# Length_Tune.net
KiCad netlist of a schematic drawn in Altium Designer
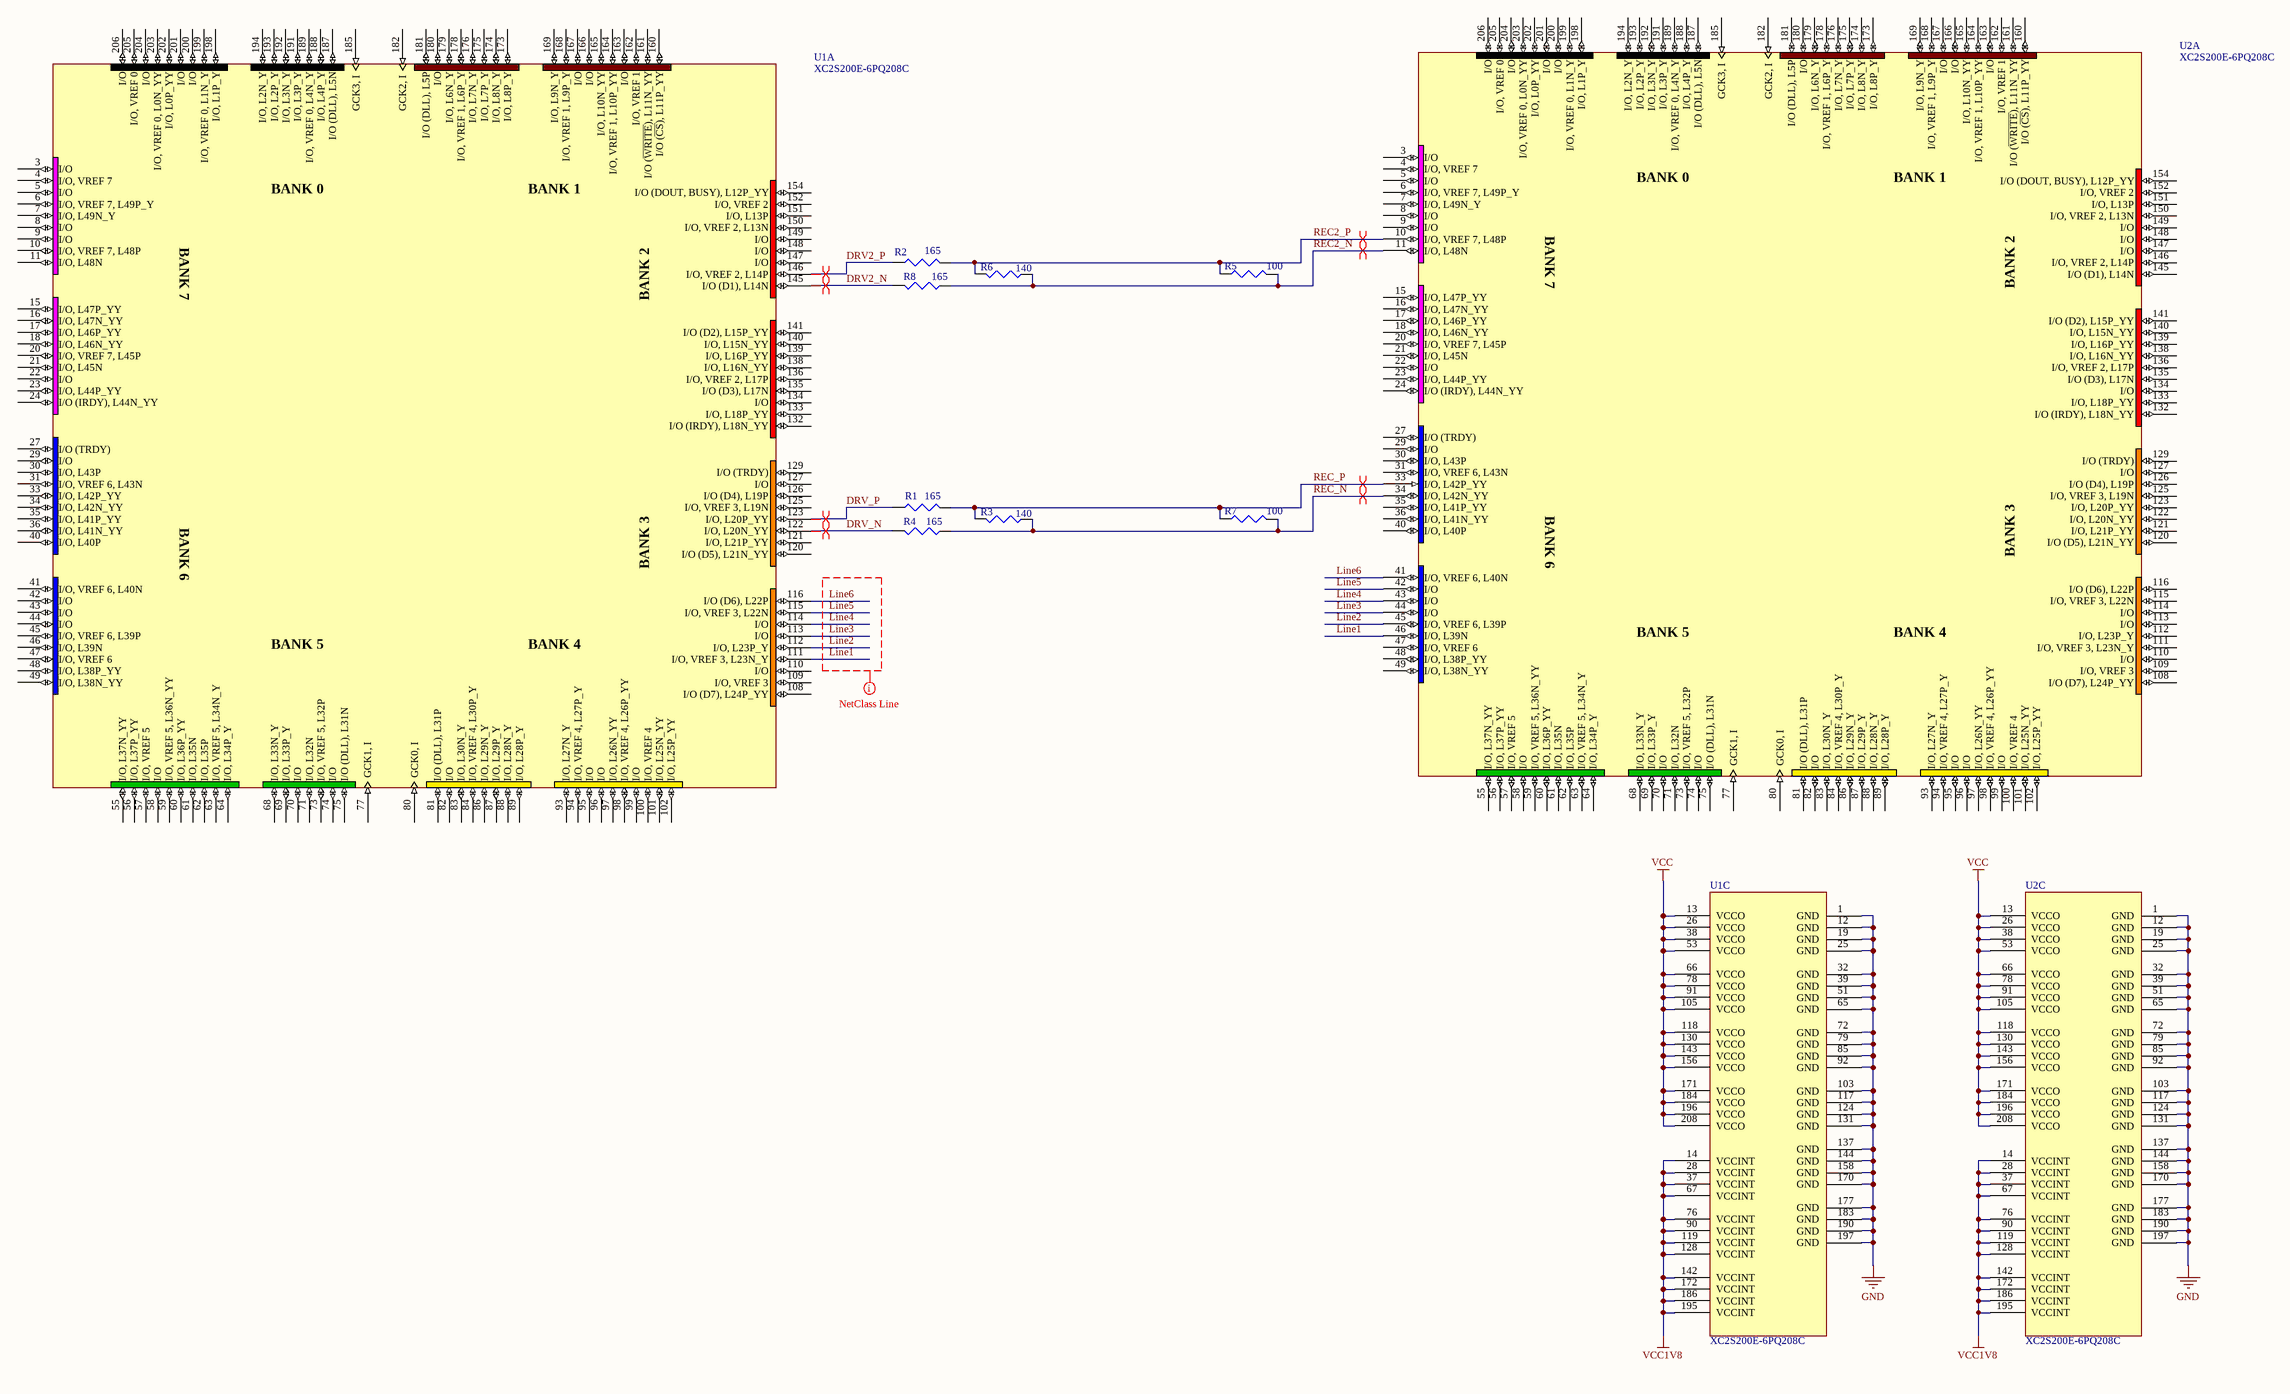
[diagram p0: Length_Tune.SchDoc]

(export (version "E")
  (design (tool "Eeschema 10.0.6"))
  (components
    (comp (ref "R1")
      (value "165")
      (footprint "J1-0603")
      (description "Resistor")
      (fields (field (name "Comment") "Res3") (field (name "PUBLISHER") "Altium Limited"))
      (libsource (lib "Miscellaneous Devices") (part "Res3"))
    )
    (comp (ref "R2")
      (value "165")
      (footprint "J1-0603")
      (description "Resistor")
      (fields (field (name "Comment") "Res3") (field (name "PUBLISHER") "Altium Limited"))
      (libsource (lib "Miscellaneous Devices") (part "Res3"))
    )
    (comp (ref "R3")
      (value "140")
      (footprint "J1-0603")
      (description "Resistor")
      (fields (field (name "Comment") "Res3") (field (name "PUBLISHER") "Altium Limited"))
      (libsource (lib "Miscellaneous Devices") (part "Res3"))
    )
    (comp (ref "R4")
      (value "165")
      (footprint "J1-0603")
      (description "Resistor")
      (fields (field (name "Comment") "Res3") (field (name "PUBLISHER") "Altium Limited"))
      (libsource (lib "Miscellaneous Devices") (part "Res3"))
    )
    (comp (ref "R5")
      (value "100")
      (footprint "J1-0603")
      (description "Resistor")
      (fields (field (name "Comment") "Res3") (field (name "PUBLISHER") "Altium Limited"))
      (libsource (lib "Miscellaneous Devices") (part "Res3"))
    )
    (comp (ref "R6")
      (value "140")
      (footprint "J1-0603")
      (description "Resistor")
      (fields (field (name "Comment") "Res3") (field (name "PUBLISHER") "Altium Limited"))
      (libsource (lib "Miscellaneous Devices") (part "Res3"))
    )
    (comp (ref "R7")
      (value "100")
      (footprint "J1-0603")
      (description "Resistor")
      (fields (field (name "Comment") "Res3") (field (name "PUBLISHER") "Altium Limited"))
      (libsource (lib "Miscellaneous Devices") (part "Res3"))
    )
    (comp (ref "R8")
      (value "165")
      (footprint "J1-0603")
      (description "Resistor")
      (fields (field (name "Comment") "Res3") (field (name "PUBLISHER") "Altium Limited"))
      (libsource (lib "Miscellaneous Devices") (part "Res3"))
    )
    (comp (ref "U1")
      (value "XC2S200E-6PQ208C")
      (footprint "PQ208")
      (description "Spartan-IIE 1.8V FPGA, 208-Pin PQFP, Standard Performance, Commercial Grade")
      (fields (field (name "PUBLISHER") "Altium Limited"))
      (libsource (lib "Xilinx Spartan-IIE") (part "XC2S200E-6PQ208C"))
    )
    (comp (ref "U2")
      (value "XC2S200E-6PQ208C")
      (footprint "PQ208")
      (description "Spartan-IIE 1.8V FPGA, 208-Pin PQFP, Standard Performance, Commercial Grade")
      (fields (field (name "PUBLISHER") "Altium Limited"))
      (libsource (lib "Xilinx Spartan-IIE") (part "XC2S200E-6PQ208C"))
    )
  )
  (nets
    (net (code "1") (name "/DRV2_N") (class "Default")
      (node (ref "R8") (pin "2") (pinfunction "2_2") (pintype "passive"))
      (node (ref "U1") (pin "145") (pinfunction "I/O_(D1),_L14N_145") (pintype "bidirectional"))
    )
    (net (code "2") (name "/DRV2_P") (class "Default")
      (node (ref "R2") (pin "1") (pinfunction "1_1") (pintype "passive"))
      (node (ref "U1") (pin "146") (pinfunction "I/O,_VREF_2,_L14P_146") (pintype "bidirectional"))
    )
    (net (code "3") (name "/DRV_N") (class "Default")
      (node (ref "R4") (pin "2") (pinfunction "2_2") (pintype "passive"))
      (node (ref "U1") (pin "122") (pinfunction "I/O,_L20N_YY_122") (pintype "bidirectional"))
    )
    (net (code "4") (name "/DRV_P") (class "Default")
      (node (ref "R1") (pin "1") (pinfunction "1_1") (pintype "passive"))
      (node (ref "U1") (pin "123") (pinfunction "I/O,_L20P_YY_123") (pintype "bidirectional"))
    )
    (net (code "5") (name "/Line1") (class "Default")
      (node (ref "U1") (pin "111") (pinfunction "I/O,_VREF_3,_L23N_Y_111") (pintype "bidirectional"))
      (node (ref "U2") (pin "46") (pinfunction "I/O,_L39N_46") (pintype "bidirectional"))
    )
    (net (code "6") (name "/Line2") (class "Default")
      (node (ref "U1") (pin "112") (pinfunction "I/O,_L23P_Y_112") (pintype "bidirectional"))
      (node (ref "U2") (pin "45") (pinfunction "I/O,_VREF_6,_L39P_45") (pintype "bidirectional"))
    )
    (net (code "7") (name "/Line3") (class "Default")
      (node (ref "U1") (pin "113") (pinfunction "I/O_113") (pintype "bidirectional"))
      (node (ref "U2") (pin "44") (pinfunction "I/O_44") (pintype "bidirectional"))
    )
    (net (code "8") (name "/Line4") (class "Default")
      (node (ref "U1") (pin "114") (pinfunction "I/O_114") (pintype "bidirectional"))
      (node (ref "U2") (pin "43") (pinfunction "I/O_43") (pintype "bidirectional"))
    )
    (net (code "9") (name "/Line5") (class "Default")
      (node (ref "U1") (pin "115") (pinfunction "I/O,_VREF_3,_L22N_115") (pintype "bidirectional"))
      (node (ref "U2") (pin "42") (pinfunction "I/O_42") (pintype "bidirectional"))
    )
    (net (code "10") (name "/Line6") (class "Default")
      (node (ref "U1") (pin "116") (pinfunction "I/O_(D6),_L22P_116") (pintype "bidirectional"))
      (node (ref "U2") (pin "41") (pinfunction "I/O,_VREF_6,_L40N_41") (pintype "bidirectional"))
    )
    (net (code "11") (name "/REC2_N") (class "Default")
      (node (ref "R5") (pin "2") (pinfunction "2_2") (pintype "passive"))
      (node (ref "R6") (pin "1") (pinfunction "1_1") (pintype "passive"))
      (node (ref "R8") (pin "1") (pinfunction "1_1") (pintype "passive"))
      (node (ref "U2") (pin "11") (pinfunction "I/O,_L48N_11") (pintype "bidirectional"))
    )
    (net (code "12") (name "/REC2_P") (class "Default")
      (node (ref "R2") (pin "2") (pinfunction "2_2") (pintype "passive"))
      (node (ref "R5") (pin "1") (pinfunction "1_1") (pintype "passive"))
      (node (ref "R6") (pin "2") (pinfunction "2_2") (pintype "passive"))
      (node (ref "U2") (pin "10") (pinfunction "I/O,_VREF_7,_L48P_10") (pintype "bidirectional"))
    )
    (net (code "13") (name "/REC_N") (class "Default")
      (node (ref "R3") (pin "1") (pinfunction "1_1") (pintype "passive"))
      (node (ref "R4") (pin "1") (pinfunction "1_1") (pintype "passive"))
      (node (ref "R7") (pin "2") (pinfunction "2_2") (pintype "passive"))
      (node (ref "U2") (pin "34") (pinfunction "I/O,_L42N_YY_34") (pintype "bidirectional"))
    )
    (net (code "14") (name "/REC_P") (class "Default")
      (node (ref "R1") (pin "2") (pinfunction "2_2") (pintype "passive"))
      (node (ref "R3") (pin "2") (pinfunction "2_2") (pintype "passive"))
      (node (ref "R7") (pin "1") (pinfunction "1_1") (pintype "passive"))
      (node (ref "U2") (pin "33") (pinfunction "I/O,_L42P_YY_33") (pintype "bidirectional"))
    )
    (net (code "15") (name "GND") (class "Default")
      (node (ref "U1") (pin "1") (pinfunction "GND_1") (pintype "power_in"))
      (node (ref "U1") (pin "103") (pinfunction "GND_103") (pintype "power_in"))
      (node (ref "U1") (pin "117") (pinfunction "GND_117") (pintype "power_in"))
      (node (ref "U1") (pin "12") (pinfunction "GND_12") (pintype "power_in"))
      (node (ref "U1") (pin "124") (pinfunction "GND_124") (pintype "power_in"))
      (node (ref "U1") (pin "131") (pinfunction "GND_131") (pintype "power_in"))
      (node (ref "U1") (pin "137") (pinfunction "GND_137") (pintype "power_in"))
      (node (ref "U1") (pin "144") (pinfunction "GND_144") (pintype "power_in"))
      (node (ref "U1") (pin "158") (pinfunction "GND_158") (pintype "power_in"))
      (node (ref "U1") (pin "170") (pinfunction "GND_170") (pintype "power_in"))
      (node (ref "U1") (pin "177") (pinfunction "GND_177") (pintype "power_in"))
      (node (ref "U1") (pin "183") (pinfunction "GND_183") (pintype "power_in"))
      (node (ref "U1") (pin "19") (pinfunction "GND_19") (pintype "power_in"))
      (node (ref "U1") (pin "190") (pinfunction "GND_190") (pintype "power_in"))
      (node (ref "U1") (pin "197") (pinfunction "GND_197") (pintype "power_in"))
      (node (ref "U1") (pin "25") (pinfunction "GND_25") (pintype "power_in"))
      (node (ref "U1") (pin "32") (pinfunction "GND_32") (pintype "power_in"))
      (node (ref "U1") (pin "39") (pinfunction "GND_39") (pintype "power_in"))
      (node (ref "U1") (pin "51") (pinfunction "GND_51") (pintype "power_in"))
      (node (ref "U1") (pin "65") (pinfunction "GND_65") (pintype "power_in"))
      (node (ref "U1") (pin "72") (pinfunction "GND_72") (pintype "power_in"))
      (node (ref "U1") (pin "79") (pinfunction "GND_79") (pintype "power_in"))
      (node (ref "U1") (pin "85") (pinfunction "GND_85") (pintype "power_in"))
      (node (ref "U1") (pin "92") (pinfunction "GND_92") (pintype "power_in"))
      (node (ref "U2") (pin "1") (pinfunction "GND_1") (pintype "power_in"))
      (node (ref "U2") (pin "103") (pinfunction "GND_103") (pintype "power_in"))
      (node (ref "U2") (pin "117") (pinfunction "GND_117") (pintype "power_in"))
      (node (ref "U2") (pin "12") (pinfunction "GND_12") (pintype "power_in"))
      (node (ref "U2") (pin "124") (pinfunction "GND_124") (pintype "power_in"))
      (node (ref "U2") (pin "131") (pinfunction "GND_131") (pintype "power_in"))
      (node (ref "U2") (pin "137") (pinfunction "GND_137") (pintype "power_in"))
      (node (ref "U2") (pin "144") (pinfunction "GND_144") (pintype "power_in"))
      (node (ref "U2") (pin "158") (pinfunction "GND_158") (pintype "power_in"))
      (node (ref "U2") (pin "170") (pinfunction "GND_170") (pintype "power_in"))
      (node (ref "U2") (pin "177") (pinfunction "GND_177") (pintype "power_in"))
      (node (ref "U2") (pin "183") (pinfunction "GND_183") (pintype "power_in"))
      (node (ref "U2") (pin "19") (pinfunction "GND_19") (pintype "power_in"))
      (node (ref "U2") (pin "190") (pinfunction "GND_190") (pintype "power_in"))
      (node (ref "U2") (pin "197") (pinfunction "GND_197") (pintype "power_in"))
      (node (ref "U2") (pin "25") (pinfunction "GND_25") (pintype "power_in"))
      (node (ref "U2") (pin "32") (pinfunction "GND_32") (pintype "power_in"))
      (node (ref "U2") (pin "39") (pinfunction "GND_39") (pintype "power_in"))
      (node (ref "U2") (pin "51") (pinfunction "GND_51") (pintype "power_in"))
      (node (ref "U2") (pin "65") (pinfunction "GND_65") (pintype "power_in"))
      (node (ref "U2") (pin "72") (pinfunction "GND_72") (pintype "power_in"))
      (node (ref "U2") (pin "79") (pinfunction "GND_79") (pintype "power_in"))
      (node (ref "U2") (pin "85") (pinfunction "GND_85") (pintype "power_in"))
      (node (ref "U2") (pin "92") (pinfunction "GND_92") (pintype "power_in"))
    )
    (net (code "16") (name "VCC") (class "Default")
      (node (ref "U1") (pin "105") (pinfunction "VCCO_105") (pintype "power_in"))
      (node (ref "U1") (pin "118") (pinfunction "VCCO_118") (pintype "power_in"))
      (node (ref "U1") (pin "13") (pinfunction "VCCO_13") (pintype "power_in"))
      (node (ref "U1") (pin "130") (pinfunction "VCCO_130") (pintype "power_in"))
      (node (ref "U1") (pin "143") (pinfunction "VCCO_143") (pintype "power_in"))
      (node (ref "U1") (pin "156") (pinfunction "VCCO_156") (pintype "power_in"))
      (node (ref "U1") (pin "171") (pinfunction "VCCO_171") (pintype "power_in"))
      (node (ref "U1") (pin "184") (pinfunction "VCCO_184") (pintype "power_in"))
      (node (ref "U1") (pin "196") (pinfunction "VCCO_196") (pintype "power_in"))
      (node (ref "U1") (pin "208") (pinfunction "VCCO_208") (pintype "power_in"))
      (node (ref "U1") (pin "26") (pinfunction "VCCO_26") (pintype "power_in"))
      (node (ref "U1") (pin "38") (pinfunction "VCCO_38") (pintype "power_in"))
      (node (ref "U1") (pin "53") (pinfunction "VCCO_53") (pintype "power_in"))
      (node (ref "U1") (pin "66") (pinfunction "VCCO_66") (pintype "power_in"))
      (node (ref "U1") (pin "78") (pinfunction "VCCO_78") (pintype "power_in"))
      (node (ref "U1") (pin "91") (pinfunction "VCCO_91") (pintype "power_in"))
      (node (ref "U2") (pin "105") (pinfunction "VCCO_105") (pintype "power_in"))
      (node (ref "U2") (pin "118") (pinfunction "VCCO_118") (pintype "power_in"))
      (node (ref "U2") (pin "13") (pinfunction "VCCO_13") (pintype "power_in"))
      (node (ref "U2") (pin "130") (pinfunction "VCCO_130") (pintype "power_in"))
      (node (ref "U2") (pin "143") (pinfunction "VCCO_143") (pintype "power_in"))
      (node (ref "U2") (pin "156") (pinfunction "VCCO_156") (pintype "power_in"))
      (node (ref "U2") (pin "171") (pinfunction "VCCO_171") (pintype "power_in"))
      (node (ref "U2") (pin "184") (pinfunction "VCCO_184") (pintype "power_in"))
      (node (ref "U2") (pin "196") (pinfunction "VCCO_196") (pintype "power_in"))
      (node (ref "U2") (pin "208") (pinfunction "VCCO_208") (pintype "power_in"))
      (node (ref "U2") (pin "26") (pinfunction "VCCO_26") (pintype "power_in"))
      (node (ref "U2") (pin "38") (pinfunction "VCCO_38") (pintype "power_in"))
      (node (ref "U2") (pin "53") (pinfunction "VCCO_53") (pintype "power_in"))
      (node (ref "U2") (pin "66") (pinfunction "VCCO_66") (pintype "power_in"))
      (node (ref "U2") (pin "78") (pinfunction "VCCO_78") (pintype "power_in"))
      (node (ref "U2") (pin "91") (pinfunction "VCCO_91") (pintype "power_in"))
    )
    (net (code "17") (name "VCC1V8") (class "Default")
      (node (ref "U1") (pin "119") (pinfunction "VCCINT_119") (pintype "power_in"))
      (node (ref "U1") (pin "128") (pinfunction "VCCINT_128") (pintype "power_in"))
      (node (ref "U1") (pin "14") (pinfunction "VCCINT_14") (pintype "power_in"))
      (node (ref "U1") (pin "142") (pinfunction "VCCINT_142") (pintype "power_in"))
      (node (ref "U1") (pin "172") (pinfunction "VCCINT_172") (pintype "power_in"))
      (node (ref "U1") (pin "186") (pinfunction "VCCINT_186") (pintype "power_in"))
      (node (ref "U1") (pin "195") (pinfunction "VCCINT_195") (pintype "power_in"))
      (node (ref "U1") (pin "28") (pinfunction "VCCINT_28") (pintype "power_in"))
      (node (ref "U1") (pin "37") (pinfunction "VCCINT_37") (pintype "power_in"))
      (node (ref "U1") (pin "67") (pinfunction "VCCINT_67") (pintype "power_in"))
      (node (ref "U1") (pin "76") (pinfunction "VCCINT_76") (pintype "power_in"))
      (node (ref "U1") (pin "90") (pinfunction "VCCINT_90") (pintype "power_in"))
      (node (ref "U2") (pin "119") (pinfunction "VCCINT_119") (pintype "power_in"))
      (node (ref "U2") (pin "128") (pinfunction "VCCINT_128") (pintype "power_in"))
      (node (ref "U2") (pin "14") (pinfunction "VCCINT_14") (pintype "power_in"))
      (node (ref "U2") (pin "142") (pinfunction "VCCINT_142") (pintype "power_in"))
      (node (ref "U2") (pin "172") (pinfunction "VCCINT_172") (pintype "power_in"))
      (node (ref "U2") (pin "186") (pinfunction "VCCINT_186") (pintype "power_in"))
      (node (ref "U2") (pin "195") (pinfunction "VCCINT_195") (pintype "power_in"))
      (node (ref "U2") (pin "28") (pinfunction "VCCINT_28") (pintype "power_in"))
      (node (ref "U2") (pin "37") (pinfunction "VCCINT_37") (pintype "power_in"))
      (node (ref "U2") (pin "67") (pinfunction "VCCINT_67") (pintype "power_in"))
      (node (ref "U2") (pin "76") (pinfunction "VCCINT_76") (pintype "power_in"))
      (node (ref "U2") (pin "90") (pinfunction "VCCINT_90") (pintype "power_in"))
    )
    (net (code "18") (name "unconnected-(U1A-GCK0,_I-Pad80)") (class "Default")
      (node (ref "U1") (pin "80") (pinfunction "GCK0,_I_80") (pintype "input"))
    )
    (net (code "19") (name "unconnected-(U1A-GCK1,_I-Pad77)") (class "Default")
      (node (ref "U1") (pin "77") (pinfunction "GCK1,_I_77") (pintype "input"))
    )
    (net (code "20") (name "unconnected-(U1A-GCK2,_I-Pad182)") (class "Default")
      (node (ref "U1") (pin "182") (pinfunction "GCK2,_I_182") (pintype "input"))
    )
    (net (code "21") (name "unconnected-(U1A-GCK3,_I-Pad185)") (class "Default")
      (node (ref "U1") (pin "185") (pinfunction "GCK3,_I_185") (pintype "input"))
    )
    (net (code "22") (name "unconnected-(U1A-I{slash}O,_L0P_YY-Pad202)") (class "Default")
      (node (ref "U1") (pin "202") (pinfunction "I/O,_L0P_YY_202") (pintype "bidirectional"))
    )
    (net (code "23") (name "unconnected-(U1A-I{slash}O,_L1P_Y-Pad198)") (class "Default")
      (node (ref "U1") (pin "198") (pinfunction "I/O,_L1P_Y_198") (pintype "bidirectional"))
    )
    (net (code "24") (name "unconnected-(U1A-I{slash}O,_L2N_Y-Pad194)") (class "Default")
      (node (ref "U1") (pin "194") (pinfunction "I/O,_L2N_Y_194") (pintype "bidirectional"))
    )
    (net (code "25") (name "unconnected-(U1A-I{slash}O,_L2P_Y-Pad193)") (class "Default")
      (node (ref "U1") (pin "193") (pinfunction "I/O,_L2P_Y_193") (pintype "bidirectional"))
    )
    (net (code "26") (name "unconnected-(U1A-I{slash}O,_L3N_Y-Pad192)") (class "Default")
      (node (ref "U1") (pin "192") (pinfunction "I/O,_L3N_Y_192") (pintype "bidirectional"))
    )
    (net (code "27") (name "unconnected-(U1A-I{slash}O,_L3P_Y-Pad191)") (class "Default")
      (node (ref "U1") (pin "191") (pinfunction "I/O,_L3P_Y_191") (pintype "bidirectional"))
    )
    (net (code "28") (name "unconnected-(U1A-I{slash}O,_L4P_Y-Pad188)") (class "Default")
      (node (ref "U1") (pin "188") (pinfunction "I/O,_L4P_Y_188") (pintype "bidirectional"))
    )
    (net (code "29") (name "unconnected-(U1A-I{slash}O,_L6N_Y-Pad179)") (class "Default")
      (node (ref "U1") (pin "179") (pinfunction "I/O,_L6N_Y_179") (pintype "bidirectional"))
    )
    (net (code "30") (name "unconnected-(U1A-I{slash}O,_L7N_Y-Pad176)") (class "Default")
      (node (ref "U1") (pin "176") (pinfunction "I/O,_L7N_Y_176") (pintype "bidirectional"))
    )
    (net (code "31") (name "unconnected-(U1A-I{slash}O,_L7P_Y-Pad175)") (class "Default")
      (node (ref "U1") (pin "175") (pinfunction "I/O,_L7P_Y_175") (pintype "bidirectional"))
    )
    (net (code "32") (name "unconnected-(U1A-I{slash}O,_L8N_Y-Pad174)") (class "Default")
      (node (ref "U1") (pin "174") (pinfunction "I/O,_L8N_Y_174") (pintype "bidirectional"))
    )
    (net (code "33") (name "unconnected-(U1A-I{slash}O,_L8P_Y-Pad173)") (class "Default")
      (node (ref "U1") (pin "173") (pinfunction "I/O,_L8P_Y_173") (pintype "bidirectional"))
    )
    (net (code "34") (name "unconnected-(U1A-I{slash}O,_L9N_Y-Pad169)") (class "Default")
      (node (ref "U1") (pin "169") (pinfunction "I/O,_L9N_Y_169") (pintype "bidirectional"))
    )
    (net (code "35") (name "unconnected-(U1A-I{slash}O,_L10N_YY-Pad165)") (class "Default")
      (node (ref "U1") (pin "165") (pinfunction "I/O,_L10N_YY_165") (pintype "bidirectional"))
    )
    (net (code "36") (name "unconnected-(U1A-I{slash}O,_L13P-Pad151)") (class "Default")
      (node (ref "U1") (pin "151") (pinfunction "I/O,_L13P_151") (pintype "bidirectional"))
    )
    (net (code "37") (name "unconnected-(U1A-I{slash}O,_L15N_YY-Pad140)") (class "Default")
      (node (ref "U1") (pin "140") (pinfunction "I/O,_L15N_YY_140") (pintype "bidirectional"))
    )
    (net (code "38") (name "unconnected-(U1A-I{slash}O,_L16N_YY-Pad138)") (class "Default")
      (node (ref "U1") (pin "138") (pinfunction "I/O,_L16N_YY_138") (pintype "bidirectional"))
    )
    (net (code "39") (name "unconnected-(U1A-I{slash}O,_L16P_YY-Pad139)") (class "Default")
      (node (ref "U1") (pin "139") (pinfunction "I/O,_L16P_YY_139") (pintype "bidirectional"))
    )
    (net (code "40") (name "unconnected-(U1A-I{slash}O,_L18P_YY-Pad133)") (class "Default")
      (node (ref "U1") (pin "133") (pinfunction "I/O,_L18P_YY_133") (pintype "bidirectional"))
    )
    (net (code "41") (name "unconnected-(U1A-I{slash}O,_L21P_YY-Pad121)") (class "Default")
      (node (ref "U1") (pin "121") (pinfunction "I/O,_L21P_YY_121") (pintype "bidirectional"))
    )
    (net (code "42") (name "unconnected-(U1A-I{slash}O,_L25N_YY-Pad101)") (class "Default")
      (node (ref "U1") (pin "101") (pinfunction "I/O,_L25N_YY_101") (pintype "bidirectional"))
    )
    (net (code "43") (name "unconnected-(U1A-I{slash}O,_L25P_YY-Pad102)") (class "Default")
      (node (ref "U1") (pin "102") (pinfunction "I/O,_L25P_YY_102") (pintype "bidirectional"))
    )
    (net (code "44") (name "unconnected-(U1A-I{slash}O,_L26N_YY-Pad97)") (class "Default")
      (node (ref "U1") (pin "97") (pinfunction "I/O,_L26N_YY_97") (pintype "bidirectional"))
    )
    (net (code "45") (name "unconnected-(U1A-I{slash}O,_L27N_Y-Pad93)") (class "Default")
      (node (ref "U1") (pin "93") (pinfunction "I/O,_L27N_Y_93") (pintype "bidirectional"))
    )
    (net (code "46") (name "unconnected-(U1A-I{slash}O,_L28N_Y-Pad88)") (class "Default")
      (node (ref "U1") (pin "88") (pinfunction "I/O,_L28N_Y_88") (pintype "bidirectional"))
    )
    (net (code "47") (name "unconnected-(U1A-I{slash}O,_L28P_Y-Pad89)") (class "Default")
      (node (ref "U1") (pin "89") (pinfunction "I/O,_L28P_Y_89") (pintype "bidirectional"))
    )
    (net (code "48") (name "unconnected-(U1A-I{slash}O,_L29N_Y-Pad86)") (class "Default")
      (node (ref "U1") (pin "86") (pinfunction "I/O,_L29N_Y_86") (pintype "bidirectional"))
    )
    (net (code "49") (name "unconnected-(U1A-I{slash}O,_L29P_Y-Pad87)") (class "Default")
      (node (ref "U1") (pin "87") (pinfunction "I/O,_L29P_Y_87") (pintype "bidirectional"))
    )
    (net (code "50") (name "unconnected-(U1A-I{slash}O,_L30N_Y-Pad83)") (class "Default")
      (node (ref "U1") (pin "83") (pinfunction "I/O,_L30N_Y_83") (pintype "bidirectional"))
    )
    (net (code "51") (name "unconnected-(U1A-I{slash}O,_L32N-Pad71)") (class "Default")
      (node (ref "U1") (pin "71") (pinfunction "I/O,_L32N_71") (pintype "bidirectional"))
    )
    (net (code "52") (name "unconnected-(U1A-I{slash}O,_L33N_Y-Pad68)") (class "Default")
      (node (ref "U1") (pin "68") (pinfunction "I/O,_L33N_Y_68") (pintype "bidirectional"))
    )
    (net (code "53") (name "unconnected-(U1A-I{slash}O,_L33P_Y-Pad69)") (class "Default")
      (node (ref "U1") (pin "69") (pinfunction "I/O,_L33P_Y_69") (pintype "bidirectional"))
    )
    (net (code "54") (name "unconnected-(U1A-I{slash}O,_L34P_Y-Pad64)") (class "Default")
      (node (ref "U1") (pin "64") (pinfunction "I/O,_L34P_Y_64") (pintype "bidirectional"))
    )
    (net (code "55") (name "unconnected-(U1A-I{slash}O,_L35N-Pad61)") (class "Default")
      (node (ref "U1") (pin "61") (pinfunction "I/O,_L35N_61") (pintype "bidirectional"))
    )
    (net (code "56") (name "unconnected-(U1A-I{slash}O,_L35P-Pad62)") (class "Default")
      (node (ref "U1") (pin "62") (pinfunction "I/O,_L35P_62") (pintype "bidirectional"))
    )
    (net (code "57") (name "unconnected-(U1A-I{slash}O,_L36P_YY-Pad60)") (class "Default")
      (node (ref "U1") (pin "60") (pinfunction "I/O,_L36P_YY_60") (pintype "bidirectional"))
    )
    (net (code "58") (name "unconnected-(U1A-I{slash}O,_L37N_YY-Pad55)") (class "Default")
      (node (ref "U1") (pin "55") (pinfunction "I/O,_L37N_YY_55") (pintype "bidirectional"))
    )
    (net (code "59") (name "unconnected-(U1A-I{slash}O,_L37P_YY-Pad56)") (class "Default")
      (node (ref "U1") (pin "56") (pinfunction "I/O,_L37P_YY_56") (pintype "bidirectional"))
    )
    (net (code "60") (name "unconnected-(U1A-I{slash}O,_L38N_YY-Pad49)") (class "Default")
      (node (ref "U1") (pin "49") (pinfunction "I/O,_L38N_YY_49") (pintype "bidirectional"))
    )
    (net (code "61") (name "unconnected-(U1A-I{slash}O,_L38P_YY-Pad48)") (class "Default")
      (node (ref "U1") (pin "48") (pinfunction "I/O,_L38P_YY_48") (pintype "bidirectional"))
    )
    (net (code "62") (name "unconnected-(U1A-I{slash}O,_L39N-Pad46)") (class "Default")
      (node (ref "U1") (pin "46") (pinfunction "I/O,_L39N_46") (pintype "bidirectional"))
    )
    (net (code "63") (name "unconnected-(U1A-I{slash}O,_L40P-Pad40)") (class "Default")
      (node (ref "U1") (pin "40") (pinfunction "I/O,_L40P_40") (pintype "bidirectional"))
    )
    (net (code "64") (name "unconnected-(U1A-I{slash}O,_L41N_YY-Pad36)") (class "Default")
      (node (ref "U1") (pin "36") (pinfunction "I/O,_L41N_YY_36") (pintype "bidirectional"))
    )
    (net (code "65") (name "unconnected-(U1A-I{slash}O,_L41P_YY-Pad35)") (class "Default")
      (node (ref "U1") (pin "35") (pinfunction "I/O,_L41P_YY_35") (pintype "bidirectional"))
    )
    (net (code "66") (name "unconnected-(U1A-I{slash}O,_L42N_YY-Pad34)") (class "Default")
      (node (ref "U1") (pin "34") (pinfunction "I/O,_L42N_YY_34") (pintype "bidirectional"))
    )
    (net (code "67") (name "unconnected-(U1A-I{slash}O,_L42P_YY-Pad33)") (class "Default")
      (node (ref "U1") (pin "33") (pinfunction "I/O,_L42P_YY_33") (pintype "bidirectional"))
    )
    (net (code "68") (name "unconnected-(U1A-I{slash}O,_L43P-Pad30)") (class "Default")
      (node (ref "U1") (pin "30") (pinfunction "I/O,_L43P_30") (pintype "bidirectional"))
    )
    (net (code "69") (name "unconnected-(U1A-I{slash}O,_L44P_YY-Pad23)") (class "Default")
      (node (ref "U1") (pin "23") (pinfunction "I/O,_L44P_YY_23") (pintype "bidirectional"))
    )
    (net (code "70") (name "unconnected-(U1A-I{slash}O,_L45N-Pad21)") (class "Default")
      (node (ref "U1") (pin "21") (pinfunction "I/O,_L45N_21") (pintype "bidirectional"))
    )
    (net (code "71") (name "unconnected-(U1A-I{slash}O,_L46N_YY-Pad18)") (class "Default")
      (node (ref "U1") (pin "18") (pinfunction "I/O,_L46N_YY_18") (pintype "bidirectional"))
    )
    (net (code "72") (name "unconnected-(U1A-I{slash}O,_L46P_YY-Pad17)") (class "Default")
      (node (ref "U1") (pin "17") (pinfunction "I/O,_L46P_YY_17") (pintype "bidirectional"))
    )
    (net (code "73") (name "unconnected-(U1A-I{slash}O,_L47N_YY-Pad16)") (class "Default")
      (node (ref "U1") (pin "16") (pinfunction "I/O,_L47N_YY_16") (pintype "bidirectional"))
    )
    (net (code "74") (name "unconnected-(U1A-I{slash}O,_L47P_YY-Pad15)") (class "Default")
      (node (ref "U1") (pin "15") (pinfunction "I/O,_L47P_YY_15") (pintype "bidirectional"))
    )
    (net (code "75") (name "unconnected-(U1A-I{slash}O,_L48N-Pad11)") (class "Default")
      (node (ref "U1") (pin "11") (pinfunction "I/O,_L48N_11") (pintype "bidirectional"))
    )
    (net (code "76") (name "unconnected-(U1A-I{slash}O,_L49N_Y-Pad7)") (class "Default")
      (node (ref "U1") (pin "7") (pinfunction "I/O,_L49N_Y_7") (pintype "bidirectional"))
    )
    (net (code "77") (name "unconnected-(U1A-I{slash}O,_VREF_0,_L0N_YY-Pad203)") (class "Default")
      (node (ref "U1") (pin "203") (pinfunction "I/O,_VREF_0,_L0N_YY_203") (pintype "bidirectional"))
    )
    (net (code "78") (name "unconnected-(U1A-I{slash}O,_VREF_0,_L1N_Y-Pad199)") (class "Default")
      (node (ref "U1") (pin "199") (pinfunction "I/O,_VREF_0,_L1N_Y_199") (pintype "bidirectional"))
    )
    (net (code "79") (name "unconnected-(U1A-I{slash}O,_VREF_0,_L4N_Y-Pad189)") (class "Default")
      (node (ref "U1") (pin "189") (pinfunction "I/O,_VREF_0,_L4N_Y_189") (pintype "bidirectional"))
    )
    (net (code "80") (name "unconnected-(U1A-I{slash}O,_VREF_0-Pad205)") (class "Default")
      (node (ref "U1") (pin "205") (pinfunction "I/O,_VREF_0_205") (pintype "bidirectional"))
    )
    (net (code "81") (name "unconnected-(U1A-I{slash}O,_VREF_1,_L6P_Y-Pad178)") (class "Default")
      (node (ref "U1") (pin "178") (pinfunction "I/O,_VREF_1,_L6P_Y_178") (pintype "bidirectional"))
    )
    (net (code "82") (name "unconnected-(U1A-I{slash}O,_VREF_1,_L9P_Y-Pad168)") (class "Default")
      (node (ref "U1") (pin "168") (pinfunction "I/O,_VREF_1,_L9P_Y_168") (pintype "bidirectional"))
    )
    (net (code "83") (name "unconnected-(U1A-I{slash}O,_VREF_1,_L10P_YY-Pad164)") (class "Default")
      (node (ref "U1") (pin "164") (pinfunction "I/O,_VREF_1,_L10P_YY_164") (pintype "bidirectional"))
    )
    (net (code "84") (name "unconnected-(U1A-I{slash}O,_VREF_1-Pad162)") (class "Default")
      (node (ref "U1") (pin "162") (pinfunction "I/O,_VREF_1_162") (pintype "bidirectional"))
    )
    (net (code "85") (name "unconnected-(U1A-I{slash}O,_VREF_2,_L13N-Pad150)") (class "Default")
      (node (ref "U1") (pin "150") (pinfunction "I/O,_VREF_2,_L13N_150") (pintype "bidirectional"))
    )
    (net (code "86") (name "unconnected-(U1A-I{slash}O,_VREF_2,_L17P-Pad136)") (class "Default")
      (node (ref "U1") (pin "136") (pinfunction "I/O,_VREF_2,_L17P_136") (pintype "bidirectional"))
    )
    (net (code "87") (name "unconnected-(U1A-I{slash}O,_VREF_2-Pad152)") (class "Default")
      (node (ref "U1") (pin "152") (pinfunction "I/O,_VREF_2_152") (pintype "bidirectional"))
    )
    (net (code "88") (name "unconnected-(U1A-I{slash}O,_VREF_3,_L19N-Pad125)") (class "Default")
      (node (ref "U1") (pin "125") (pinfunction "I/O,_VREF_3,_L19N_125") (pintype "bidirectional"))
    )
    (net (code "89") (name "unconnected-(U1A-I{slash}O,_VREF_3-Pad109)") (class "Default")
      (node (ref "U1") (pin "109") (pinfunction "I/O,_VREF_3_109") (pintype "bidirectional"))
    )
    (net (code "90") (name "unconnected-(U1A-I{slash}O,_VREF_4,_L26P_YY-Pad98)") (class "Default")
      (node (ref "U1") (pin "98") (pinfunction "I/O,_VREF_4,_L26P_YY_98") (pintype "bidirectional"))
    )
    (net (code "91") (name "unconnected-(U1A-I{slash}O,_VREF_4,_L27P_Y-Pad94)") (class "Default")
      (node (ref "U1") (pin "94") (pinfunction "I/O,_VREF_4,_L27P_Y_94") (pintype "bidirectional"))
    )
    (net (code "92") (name "unconnected-(U1A-I{slash}O,_VREF_4,_L30P_Y-Pad84)") (class "Default")
      (node (ref "U1") (pin "84") (pinfunction "I/O,_VREF_4,_L30P_Y_84") (pintype "bidirectional"))
    )
    (net (code "93") (name "unconnected-(U1A-I{slash}O,_VREF_4-Pad100)") (class "Default")
      (node (ref "U1") (pin "100") (pinfunction "I/O,_VREF_4_100") (pintype "bidirectional"))
    )
    (net (code "94") (name "unconnected-(U1A-I{slash}O,_VREF_5,_L32P-Pad73)") (class "Default")
      (node (ref "U1") (pin "73") (pinfunction "I/O,_VREF_5,_L32P_73") (pintype "bidirectional"))
    )
    (net (code "95") (name "unconnected-(U1A-I{slash}O,_VREF_5,_L34N_Y-Pad63)") (class "Default")
      (node (ref "U1") (pin "63") (pinfunction "I/O,_VREF_5,_L34N_Y_63") (pintype "bidirectional"))
    )
    (net (code "96") (name "unconnected-(U1A-I{slash}O,_VREF_5,_L36N_YY-Pad59)") (class "Default")
      (node (ref "U1") (pin "59") (pinfunction "I/O,_VREF_5,_L36N_YY_59") (pintype "bidirectional"))
    )
    (net (code "97") (name "unconnected-(U1A-I{slash}O,_VREF_5-Pad57)") (class "Default")
      (node (ref "U1") (pin "57") (pinfunction "I/O,_VREF_5_57") (pintype "bidirectional"))
    )
    (net (code "98") (name "unconnected-(U1A-I{slash}O,_VREF_6,_L39P-Pad45)") (class "Default")
      (node (ref "U1") (pin "45") (pinfunction "I/O,_VREF_6,_L39P_45") (pintype "bidirectional"))
    )
    (net (code "99") (name "unconnected-(U1A-I{slash}O,_VREF_6,_L40N-Pad41)") (class "Default")
      (node (ref "U1") (pin "41") (pinfunction "I/O,_VREF_6,_L40N_41") (pintype "bidirectional"))
    )
    (net (code "100") (name "unconnected-(U1A-I{slash}O,_VREF_6,_L43N-Pad31)") (class "Default")
      (node (ref "U1") (pin "31") (pinfunction "I/O,_VREF_6,_L43N_31") (pintype "bidirectional"))
    )
    (net (code "101") (name "unconnected-(U1A-I{slash}O,_VREF_6-Pad47)") (class "Default")
      (node (ref "U1") (pin "47") (pinfunction "I/O,_VREF_6_47") (pintype "bidirectional"))
    )
    (net (code "102") (name "unconnected-(U1A-I{slash}O,_VREF_7,_L45P-Pad20)") (class "Default")
      (node (ref "U1") (pin "20") (pinfunction "I/O,_VREF_7,_L45P_20") (pintype "bidirectional"))
    )
    (net (code "103") (name "unconnected-(U1A-I{slash}O,_VREF_7,_L48P-Pad10)") (class "Default")
      (node (ref "U1") (pin "10") (pinfunction "I/O,_VREF_7,_L48P_10") (pintype "bidirectional"))
    )
    (net (code "104") (name "unconnected-(U1A-I{slash}O,_VREF_7,_L49P_Y-Pad6)") (class "Default")
      (node (ref "U1") (pin "6") (pinfunction "I/O,_VREF_7,_L49P_Y_6") (pintype "bidirectional"))
    )
    (net (code "105") (name "unconnected-(U1A-I{slash}O,_VREF_7-Pad4)") (class "Default")
      (node (ref "U1") (pin "4") (pinfunction "I/O,_VREF_7_4") (pintype "bidirectional"))
    )
    (net (code "106") (name "unconnected-(U1A-I{slash}O-Pad3)") (class "Default")
      (node (ref "U1") (pin "3") (pinfunction "I/O_3") (pintype "bidirectional"))
    )
    (net (code "107") (name "unconnected-(U1A-I{slash}O-Pad5)") (class "Default")
      (node (ref "U1") (pin "5") (pinfunction "I/O_5") (pintype "bidirectional"))
    )
    (net (code "108") (name "unconnected-(U1A-I{slash}O-Pad8)") (class "Default")
      (node (ref "U1") (pin "8") (pinfunction "I/O_8") (pintype "bidirectional"))
    )
    (net (code "109") (name "unconnected-(U1A-I{slash}O-Pad9)") (class "Default")
      (node (ref "U1") (pin "9") (pinfunction "I/O_9") (pintype "bidirectional"))
    )
    (net (code "110") (name "unconnected-(U1A-I{slash}O-Pad22)") (class "Default")
      (node (ref "U1") (pin "22") (pinfunction "I/O_22") (pintype "bidirectional"))
    )
    (net (code "111") (name "unconnected-(U1A-I{slash}O-Pad29)") (class "Default")
      (node (ref "U1") (pin "29") (pinfunction "I/O_29") (pintype "bidirectional"))
    )
    (net (code "112") (name "unconnected-(U1A-I{slash}O-Pad42)") (class "Default")
      (node (ref "U1") (pin "42") (pinfunction "I/O_42") (pintype "bidirectional"))
    )
    (net (code "113") (name "unconnected-(U1A-I{slash}O-Pad43)") (class "Default")
      (node (ref "U1") (pin "43") (pinfunction "I/O_43") (pintype "bidirectional"))
    )
    (net (code "114") (name "unconnected-(U1A-I{slash}O-Pad44)") (class "Default")
      (node (ref "U1") (pin "44") (pinfunction "I/O_44") (pintype "bidirectional"))
    )
    (net (code "115") (name "unconnected-(U1A-I{slash}O-Pad58)") (class "Default")
      (node (ref "U1") (pin "58") (pinfunction "I/O_58") (pintype "bidirectional"))
    )
    (net (code "116") (name "unconnected-(U1A-I{slash}O-Pad70)") (class "Default")
      (node (ref "U1") (pin "70") (pinfunction "I/O_70") (pintype "bidirectional"))
    )
    (net (code "117") (name "unconnected-(U1A-I{slash}O-Pad74)") (class "Default")
      (node (ref "U1") (pin "74") (pinfunction "I/O_74") (pintype "bidirectional"))
    )
    (net (code "118") (name "unconnected-(U1A-I{slash}O-Pad82)") (class "Default")
      (node (ref "U1") (pin "82") (pinfunction "I/O_82") (pintype "bidirectional"))
    )
    (net (code "119") (name "unconnected-(U1A-I{slash}O-Pad95)") (class "Default")
      (node (ref "U1") (pin "95") (pinfunction "I/O_95") (pintype "bidirectional"))
    )
    (net (code "120") (name "unconnected-(U1A-I{slash}O-Pad96)") (class "Default")
      (node (ref "U1") (pin "96") (pinfunction "I/O_96") (pintype "bidirectional"))
    )
    (net (code "121") (name "unconnected-(U1A-I{slash}O-Pad99)") (class "Default")
      (node (ref "U1") (pin "99") (pinfunction "I/O_99") (pintype "bidirectional"))
    )
    (net (code "122") (name "unconnected-(U1A-I{slash}O-Pad110)") (class "Default")
      (node (ref "U1") (pin "110") (pinfunction "I/O_110") (pintype "bidirectional"))
    )
    (net (code "123") (name "unconnected-(U1A-I{slash}O-Pad127)") (class "Default")
      (node (ref "U1") (pin "127") (pinfunction "I/O_127") (pintype "bidirectional"))
    )
    (net (code "124") (name "unconnected-(U1A-I{slash}O-Pad134)") (class "Default")
      (node (ref "U1") (pin "134") (pinfunction "I/O_134") (pintype "bidirectional"))
    )
    (net (code "125") (name "unconnected-(U1A-I{slash}O-Pad147)") (class "Default")
      (node (ref "U1") (pin "147") (pinfunction "I/O_147") (pintype "bidirectional"))
    )
    (net (code "126") (name "unconnected-(U1A-I{slash}O-Pad148)") (class "Default")
      (node (ref "U1") (pin "148") (pinfunction "I/O_148") (pintype "bidirectional"))
    )
    (net (code "127") (name "unconnected-(U1A-I{slash}O-Pad149)") (class "Default")
      (node (ref "U1") (pin "149") (pinfunction "I/O_149") (pintype "bidirectional"))
    )
    (net (code "128") (name "unconnected-(U1A-I{slash}O-Pad163)") (class "Default")
      (node (ref "U1") (pin "163") (pinfunction "I/O_163") (pintype "bidirectional"))
    )
    (net (code "129") (name "unconnected-(U1A-I{slash}O-Pad166)") (class "Default")
      (node (ref "U1") (pin "166") (pinfunction "I/O_166") (pintype "bidirectional"))
    )
    (net (code "130") (name "unconnected-(U1A-I{slash}O-Pad167)") (class "Default")
      (node (ref "U1") (pin "167") (pinfunction "I/O_167") (pintype "bidirectional"))
    )
    (net (code "131") (name "unconnected-(U1A-I{slash}O-Pad180)") (class "Default")
      (node (ref "U1") (pin "180") (pinfunction "I/O_180") (pintype "bidirectional"))
    )
    (net (code "132") (name "unconnected-(U1A-I{slash}O-Pad200)") (class "Default")
      (node (ref "U1") (pin "200") (pinfunction "I/O_200") (pintype "bidirectional"))
    )
    (net (code "133") (name "unconnected-(U1A-I{slash}O-Pad201)") (class "Default")
      (node (ref "U1") (pin "201") (pinfunction "I/O_201") (pintype "bidirectional"))
    )
    (net (code "134") (name "unconnected-(U1A-I{slash}O-Pad204)") (class "Default")
      (node (ref "U1") (pin "204") (pinfunction "I/O_204") (pintype "bidirectional"))
    )
    (net (code "135") (name "unconnected-(U1A-I{slash}O-Pad206)") (class "Default")
      (node (ref "U1") (pin "206") (pinfunction "I/O_206") (pintype "bidirectional"))
    )
    (net (code "136") (name "unconnected-(U1A-I{slash}O_(D2),_L15P_YY-Pad141)") (class "Default")
      (node (ref "U1") (pin "141") (pinfunction "I/O_(D2),_L15P_YY_141") (pintype "bidirectional"))
    )
    (net (code "137") (name "unconnected-(U1A-I{slash}O_(D3),_L17N-Pad135)") (class "Default")
      (node (ref "U1") (pin "135") (pinfunction "I/O_(D3),_L17N_135") (pintype "bidirectional"))
    )
    (net (code "138") (name "unconnected-(U1A-I{slash}O_(D4),_L19P-Pad126)") (class "Default")
      (node (ref "U1") (pin "126") (pinfunction "I/O_(D4),_L19P_126") (pintype "bidirectional"))
    )
    (net (code "139") (name "unconnected-(U1A-I{slash}O_(D5),_L21N_YY-Pad120)") (class "Default")
      (node (ref "U1") (pin "120") (pinfunction "I/O_(D5),_L21N_YY_120") (pintype "bidirectional"))
    )
    (net (code "140") (name "unconnected-(U1A-I{slash}O_(D7),_L24P_YY-Pad108)") (class "Default")
      (node (ref "U1") (pin "108") (pinfunction "I/O_(D7),_L24P_YY_108") (pintype "bidirectional"))
    )
    (net (code "141") (name "unconnected-(U1A-I{slash}O_(DLL),_L5N-Pad187)") (class "Default")
      (node (ref "U1") (pin "187") (pinfunction "I/O_(DLL),_L5N_187") (pintype "bidirectional"))
    )
    (net (code "142") (name "unconnected-(U1A-I{slash}O_(DLL),_L5P-Pad181)") (class "Default")
      (node (ref "U1") (pin "181") (pinfunction "I/O_(DLL),_L5P_181") (pintype "bidirectional"))
    )
    (net (code "143") (name "unconnected-(U1A-I{slash}O_(DLL),_L31N-Pad75)") (class "Default")
      (node (ref "U1") (pin "75") (pinfunction "I/O_(DLL),_L31N_75") (pintype "bidirectional"))
    )
    (net (code "144") (name "unconnected-(U1A-I{slash}O_(DLL),_L31P-Pad81)") (class "Default")
      (node (ref "U1") (pin "81") (pinfunction "I/O_(DLL),_L31P_81") (pintype "bidirectional"))
    )
    (net (code "145") (name "unconnected-(U1A-I{slash}O_(DOUT,_BUSY),_L12P_YY-Pad154)") (class "Default")
      (node (ref "U1") (pin "154") (pinfunction "I/O_(DOUT,_BUSY),_L12P_YY_154") (pintype "bidirectional"))
    )
    (net (code "146") (name "unconnected-(U1A-I{slash}O_(IRDY),_L18N_YY-Pad132)") (class "Default")
      (node (ref "U1") (pin "132") (pinfunction "I/O_(IRDY),_L18N_YY_132") (pintype "bidirectional"))
    )
    (net (code "147") (name "unconnected-(U1A-I{slash}O_(IRDY),_L44N_YY-Pad24)") (class "Default")
      (node (ref "U1") (pin "24") (pinfunction "I/O_(IRDY),_L44N_YY_24") (pintype "bidirectional"))
    )
    (net (code "148") (name "unconnected-(U1A-I{slash}O_(TRDY)-Pad27)") (class "Default")
      (node (ref "U1") (pin "27") (pinfunction "I/O_(TRDY)_27") (pintype "bidirectional"))
    )
    (net (code "149") (name "unconnected-(U1A-I{slash}O_(TRDY)-Pad129)") (class "Default")
      (node (ref "U1") (pin "129") (pinfunction "I/O_(TRDY)_129") (pintype "bidirectional"))
    )
    (net (code "150") (name "unconnected-(U1A-I{slash}O_(~{CS}),_L11P_YY-Pad160)") (class "Default")
      (node (ref "U1") (pin "160") (pinfunction "I/O_(~{CS}),_L11P_YY_160") (pintype "bidirectional"))
    )
    (net (code "151") (name "unconnected-(U1A-I{slash}O_(~{WRITE}),_L11N_YY-Pad161)") (class "Default")
      (node (ref "U1") (pin "161") (pinfunction "I/O_(~{WRITE}),_L11N_YY_161") (pintype "bidirectional"))
    )
    (net (code "152") (name "unconnected-(U2A-GCK0,_I-Pad80)") (class "Default")
      (node (ref "U2") (pin "80") (pinfunction "GCK0,_I_80") (pintype "input"))
    )
    (net (code "153") (name "unconnected-(U2A-GCK1,_I-Pad77)") (class "Default")
      (node (ref "U2") (pin "77") (pinfunction "GCK1,_I_77") (pintype "input"))
    )
    (net (code "154") (name "unconnected-(U2A-GCK2,_I-Pad182)") (class "Default")
      (node (ref "U2") (pin "182") (pinfunction "GCK2,_I_182") (pintype "input"))
    )
    (net (code "155") (name "unconnected-(U2A-GCK3,_I-Pad185)") (class "Default")
      (node (ref "U2") (pin "185") (pinfunction "GCK3,_I_185") (pintype "input"))
    )
    (net (code "156") (name "unconnected-(U2A-I{slash}O,_L0P_YY-Pad202)") (class "Default")
      (node (ref "U2") (pin "202") (pinfunction "I/O,_L0P_YY_202") (pintype "bidirectional"))
    )
    (net (code "157") (name "unconnected-(U2A-I{slash}O,_L1P_Y-Pad198)") (class "Default")
      (node (ref "U2") (pin "198") (pinfunction "I/O,_L1P_Y_198") (pintype "bidirectional"))
    )
    (net (code "158") (name "unconnected-(U2A-I{slash}O,_L2N_Y-Pad194)") (class "Default")
      (node (ref "U2") (pin "194") (pinfunction "I/O,_L2N_Y_194") (pintype "bidirectional"))
    )
    (net (code "159") (name "unconnected-(U2A-I{slash}O,_L2P_Y-Pad193)") (class "Default")
      (node (ref "U2") (pin "193") (pinfunction "I/O,_L2P_Y_193") (pintype "bidirectional"))
    )
    (net (code "160") (name "unconnected-(U2A-I{slash}O,_L3N_Y-Pad192)") (class "Default")
      (node (ref "U2") (pin "192") (pinfunction "I/O,_L3N_Y_192") (pintype "bidirectional"))
    )
    (net (code "161") (name "unconnected-(U2A-I{slash}O,_L3P_Y-Pad191)") (class "Default")
      (node (ref "U2") (pin "191") (pinfunction "I/O,_L3P_Y_191") (pintype "bidirectional"))
    )
    (net (code "162") (name "unconnected-(U2A-I{slash}O,_L4P_Y-Pad188)") (class "Default")
      (node (ref "U2") (pin "188") (pinfunction "I/O,_L4P_Y_188") (pintype "bidirectional"))
    )
    (net (code "163") (name "unconnected-(U2A-I{slash}O,_L6N_Y-Pad179)") (class "Default")
      (node (ref "U2") (pin "179") (pinfunction "I/O,_L6N_Y_179") (pintype "bidirectional"))
    )
    (net (code "164") (name "unconnected-(U2A-I{slash}O,_L7N_Y-Pad176)") (class "Default")
      (node (ref "U2") (pin "176") (pinfunction "I/O,_L7N_Y_176") (pintype "bidirectional"))
    )
    (net (code "165") (name "unconnected-(U2A-I{slash}O,_L7P_Y-Pad175)") (class "Default")
      (node (ref "U2") (pin "175") (pinfunction "I/O,_L7P_Y_175") (pintype "bidirectional"))
    )
    (net (code "166") (name "unconnected-(U2A-I{slash}O,_L8N_Y-Pad174)") (class "Default")
      (node (ref "U2") (pin "174") (pinfunction "I/O,_L8N_Y_174") (pintype "bidirectional"))
    )
    (net (code "167") (name "unconnected-(U2A-I{slash}O,_L8P_Y-Pad173)") (class "Default")
      (node (ref "U2") (pin "173") (pinfunction "I/O,_L8P_Y_173") (pintype "bidirectional"))
    )
    (net (code "168") (name "unconnected-(U2A-I{slash}O,_L9N_Y-Pad169)") (class "Default")
      (node (ref "U2") (pin "169") (pinfunction "I/O,_L9N_Y_169") (pintype "bidirectional"))
    )
    (net (code "169") (name "unconnected-(U2A-I{slash}O,_L10N_YY-Pad165)") (class "Default")
      (node (ref "U2") (pin "165") (pinfunction "I/O,_L10N_YY_165") (pintype "bidirectional"))
    )
    (net (code "170") (name "unconnected-(U2A-I{slash}O,_L13P-Pad151)") (class "Default")
      (node (ref "U2") (pin "151") (pinfunction "I/O,_L13P_151") (pintype "bidirectional"))
    )
    (net (code "171") (name "unconnected-(U2A-I{slash}O,_L15N_YY-Pad140)") (class "Default")
      (node (ref "U2") (pin "140") (pinfunction "I/O,_L15N_YY_140") (pintype "bidirectional"))
    )
    (net (code "172") (name "unconnected-(U2A-I{slash}O,_L16N_YY-Pad138)") (class "Default")
      (node (ref "U2") (pin "138") (pinfunction "I/O,_L16N_YY_138") (pintype "bidirectional"))
    )
    (net (code "173") (name "unconnected-(U2A-I{slash}O,_L16P_YY-Pad139)") (class "Default")
      (node (ref "U2") (pin "139") (pinfunction "I/O,_L16P_YY_139") (pintype "bidirectional"))
    )
    (net (code "174") (name "unconnected-(U2A-I{slash}O,_L18P_YY-Pad133)") (class "Default")
      (node (ref "U2") (pin "133") (pinfunction "I/O,_L18P_YY_133") (pintype "bidirectional"))
    )
    (net (code "175") (name "unconnected-(U2A-I{slash}O,_L20N_YY-Pad122)") (class "Default")
      (node (ref "U2") (pin "122") (pinfunction "I/O,_L20N_YY_122") (pintype "bidirectional"))
    )
    (net (code "176") (name "unconnected-(U2A-I{slash}O,_L20P_YY-Pad123)") (class "Default")
      (node (ref "U2") (pin "123") (pinfunction "I/O,_L20P_YY_123") (pintype "bidirectional"))
    )
    (net (code "177") (name "unconnected-(U2A-I{slash}O,_L21P_YY-Pad121)") (class "Default")
      (node (ref "U2") (pin "121") (pinfunction "I/O,_L21P_YY_121") (pintype "bidirectional"))
    )
    (net (code "178") (name "unconnected-(U2A-I{slash}O,_L23P_Y-Pad112)") (class "Default")
      (node (ref "U2") (pin "112") (pinfunction "I/O,_L23P_Y_112") (pintype "bidirectional"))
    )
    (net (code "179") (name "unconnected-(U2A-I{slash}O,_L25N_YY-Pad101)") (class "Default")
      (node (ref "U2") (pin "101") (pinfunction "I/O,_L25N_YY_101") (pintype "bidirectional"))
    )
    (net (code "180") (name "unconnected-(U2A-I{slash}O,_L25P_YY-Pad102)") (class "Default")
      (node (ref "U2") (pin "102") (pinfunction "I/O,_L25P_YY_102") (pintype "bidirectional"))
    )
    (net (code "181") (name "unconnected-(U2A-I{slash}O,_L26N_YY-Pad97)") (class "Default")
      (node (ref "U2") (pin "97") (pinfunction "I/O,_L26N_YY_97") (pintype "bidirectional"))
    )
    (net (code "182") (name "unconnected-(U2A-I{slash}O,_L27N_Y-Pad93)") (class "Default")
      (node (ref "U2") (pin "93") (pinfunction "I/O,_L27N_Y_93") (pintype "bidirectional"))
    )
    (net (code "183") (name "unconnected-(U2A-I{slash}O,_L28N_Y-Pad88)") (class "Default")
      (node (ref "U2") (pin "88") (pinfunction "I/O,_L28N_Y_88") (pintype "bidirectional"))
    )
    (net (code "184") (name "unconnected-(U2A-I{slash}O,_L28P_Y-Pad89)") (class "Default")
      (node (ref "U2") (pin "89") (pinfunction "I/O,_L28P_Y_89") (pintype "bidirectional"))
    )
    (net (code "185") (name "unconnected-(U2A-I{slash}O,_L29N_Y-Pad86)") (class "Default")
      (node (ref "U2") (pin "86") (pinfunction "I/O,_L29N_Y_86") (pintype "bidirectional"))
    )
    (net (code "186") (name "unconnected-(U2A-I{slash}O,_L29P_Y-Pad87)") (class "Default")
      (node (ref "U2") (pin "87") (pinfunction "I/O,_L29P_Y_87") (pintype "bidirectional"))
    )
    (net (code "187") (name "unconnected-(U2A-I{slash}O,_L30N_Y-Pad83)") (class "Default")
      (node (ref "U2") (pin "83") (pinfunction "I/O,_L30N_Y_83") (pintype "bidirectional"))
    )
    (net (code "188") (name "unconnected-(U2A-I{slash}O,_L32N-Pad71)") (class "Default")
      (node (ref "U2") (pin "71") (pinfunction "I/O,_L32N_71") (pintype "bidirectional"))
    )
    (net (code "189") (name "unconnected-(U2A-I{slash}O,_L33N_Y-Pad68)") (class "Default")
      (node (ref "U2") (pin "68") (pinfunction "I/O,_L33N_Y_68") (pintype "bidirectional"))
    )
    (net (code "190") (name "unconnected-(U2A-I{slash}O,_L33P_Y-Pad69)") (class "Default")
      (node (ref "U2") (pin "69") (pinfunction "I/O,_L33P_Y_69") (pintype "bidirectional"))
    )
    (net (code "191") (name "unconnected-(U2A-I{slash}O,_L34P_Y-Pad64)") (class "Default")
      (node (ref "U2") (pin "64") (pinfunction "I/O,_L34P_Y_64") (pintype "bidirectional"))
    )
    (net (code "192") (name "unconnected-(U2A-I{slash}O,_L35N-Pad61)") (class "Default")
      (node (ref "U2") (pin "61") (pinfunction "I/O,_L35N_61") (pintype "bidirectional"))
    )
    (net (code "193") (name "unconnected-(U2A-I{slash}O,_L35P-Pad62)") (class "Default")
      (node (ref "U2") (pin "62") (pinfunction "I/O,_L35P_62") (pintype "bidirectional"))
    )
    (net (code "194") (name "unconnected-(U2A-I{slash}O,_L36P_YY-Pad60)") (class "Default")
      (node (ref "U2") (pin "60") (pinfunction "I/O,_L36P_YY_60") (pintype "bidirectional"))
    )
    (net (code "195") (name "unconnected-(U2A-I{slash}O,_L37N_YY-Pad55)") (class "Default")
      (node (ref "U2") (pin "55") (pinfunction "I/O,_L37N_YY_55") (pintype "bidirectional"))
    )
    (net (code "196") (name "unconnected-(U2A-I{slash}O,_L37P_YY-Pad56)") (class "Default")
      (node (ref "U2") (pin "56") (pinfunction "I/O,_L37P_YY_56") (pintype "bidirectional"))
    )
    (net (code "197") (name "unconnected-(U2A-I{slash}O,_L38N_YY-Pad49)") (class "Default")
      (node (ref "U2") (pin "49") (pinfunction "I/O,_L38N_YY_49") (pintype "bidirectional"))
    )
    (net (code "198") (name "unconnected-(U2A-I{slash}O,_L38P_YY-Pad48)") (class "Default")
      (node (ref "U2") (pin "48") (pinfunction "I/O,_L38P_YY_48") (pintype "bidirectional"))
    )
    (net (code "199") (name "unconnected-(U2A-I{slash}O,_L40P-Pad40)") (class "Default")
      (node (ref "U2") (pin "40") (pinfunction "I/O,_L40P_40") (pintype "bidirectional"))
    )
    (net (code "200") (name "unconnected-(U2A-I{slash}O,_L41N_YY-Pad36)") (class "Default")
      (node (ref "U2") (pin "36") (pinfunction "I/O,_L41N_YY_36") (pintype "bidirectional"))
    )
    (net (code "201") (name "unconnected-(U2A-I{slash}O,_L41P_YY-Pad35)") (class "Default")
      (node (ref "U2") (pin "35") (pinfunction "I/O,_L41P_YY_35") (pintype "bidirectional"))
    )
    (net (code "202") (name "unconnected-(U2A-I{slash}O,_L43P-Pad30)") (class "Default")
      (node (ref "U2") (pin "30") (pinfunction "I/O,_L43P_30") (pintype "bidirectional"))
    )
    (net (code "203") (name "unconnected-(U2A-I{slash}O,_L44P_YY-Pad23)") (class "Default")
      (node (ref "U2") (pin "23") (pinfunction "I/O,_L44P_YY_23") (pintype "bidirectional"))
    )
    (net (code "204") (name "unconnected-(U2A-I{slash}O,_L45N-Pad21)") (class "Default")
      (node (ref "U2") (pin "21") (pinfunction "I/O,_L45N_21") (pintype "bidirectional"))
    )
    (net (code "205") (name "unconnected-(U2A-I{slash}O,_L46N_YY-Pad18)") (class "Default")
      (node (ref "U2") (pin "18") (pinfunction "I/O,_L46N_YY_18") (pintype "bidirectional"))
    )
    (net (code "206") (name "unconnected-(U2A-I{slash}O,_L46P_YY-Pad17)") (class "Default")
      (node (ref "U2") (pin "17") (pinfunction "I/O,_L46P_YY_17") (pintype "bidirectional"))
    )
    (net (code "207") (name "unconnected-(U2A-I{slash}O,_L47N_YY-Pad16)") (class "Default")
      (node (ref "U2") (pin "16") (pinfunction "I/O,_L47N_YY_16") (pintype "bidirectional"))
    )
    (net (code "208") (name "unconnected-(U2A-I{slash}O,_L47P_YY-Pad15)") (class "Default")
      (node (ref "U2") (pin "15") (pinfunction "I/O,_L47P_YY_15") (pintype "bidirectional"))
    )
    (net (code "209") (name "unconnected-(U2A-I{slash}O,_L49N_Y-Pad7)") (class "Default")
      (node (ref "U2") (pin "7") (pinfunction "I/O,_L49N_Y_7") (pintype "bidirectional"))
    )
    (net (code "210") (name "unconnected-(U2A-I{slash}O,_VREF_0,_L0N_YY-Pad203)") (class "Default")
      (node (ref "U2") (pin "203") (pinfunction "I/O,_VREF_0,_L0N_YY_203") (pintype "bidirectional"))
    )
    (net (code "211") (name "unconnected-(U2A-I{slash}O,_VREF_0,_L1N_Y-Pad199)") (class "Default")
      (node (ref "U2") (pin "199") (pinfunction "I/O,_VREF_0,_L1N_Y_199") (pintype "bidirectional"))
    )
    (net (code "212") (name "unconnected-(U2A-I{slash}O,_VREF_0,_L4N_Y-Pad189)") (class "Default")
      (node (ref "U2") (pin "189") (pinfunction "I/O,_VREF_0,_L4N_Y_189") (pintype "bidirectional"))
    )
    (net (code "213") (name "unconnected-(U2A-I{slash}O,_VREF_0-Pad205)") (class "Default")
      (node (ref "U2") (pin "205") (pinfunction "I/O,_VREF_0_205") (pintype "bidirectional"))
    )
    (net (code "214") (name "unconnected-(U2A-I{slash}O,_VREF_1,_L6P_Y-Pad178)") (class "Default")
      (node (ref "U2") (pin "178") (pinfunction "I/O,_VREF_1,_L6P_Y_178") (pintype "bidirectional"))
    )
    (net (code "215") (name "unconnected-(U2A-I{slash}O,_VREF_1,_L9P_Y-Pad168)") (class "Default")
      (node (ref "U2") (pin "168") (pinfunction "I/O,_VREF_1,_L9P_Y_168") (pintype "bidirectional"))
    )
    (net (code "216") (name "unconnected-(U2A-I{slash}O,_VREF_1,_L10P_YY-Pad164)") (class "Default")
      (node (ref "U2") (pin "164") (pinfunction "I/O,_VREF_1,_L10P_YY_164") (pintype "bidirectional"))
    )
    (net (code "217") (name "unconnected-(U2A-I{slash}O,_VREF_1-Pad162)") (class "Default")
      (node (ref "U2") (pin "162") (pinfunction "I/O,_VREF_1_162") (pintype "bidirectional"))
    )
    (net (code "218") (name "unconnected-(U2A-I{slash}O,_VREF_2,_L13N-Pad150)") (class "Default")
      (node (ref "U2") (pin "150") (pinfunction "I/O,_VREF_2,_L13N_150") (pintype "bidirectional"))
    )
    (net (code "219") (name "unconnected-(U2A-I{slash}O,_VREF_2,_L14P-Pad146)") (class "Default")
      (node (ref "U2") (pin "146") (pinfunction "I/O,_VREF_2,_L14P_146") (pintype "bidirectional"))
    )
    (net (code "220") (name "unconnected-(U2A-I{slash}O,_VREF_2,_L17P-Pad136)") (class "Default")
      (node (ref "U2") (pin "136") (pinfunction "I/O,_VREF_2,_L17P_136") (pintype "bidirectional"))
    )
    (net (code "221") (name "unconnected-(U2A-I{slash}O,_VREF_2-Pad152)") (class "Default")
      (node (ref "U2") (pin "152") (pinfunction "I/O,_VREF_2_152") (pintype "bidirectional"))
    )
    (net (code "222") (name "unconnected-(U2A-I{slash}O,_VREF_3,_L19N-Pad125)") (class "Default")
      (node (ref "U2") (pin "125") (pinfunction "I/O,_VREF_3,_L19N_125") (pintype "bidirectional"))
    )
    (net (code "223") (name "unconnected-(U2A-I{slash}O,_VREF_3,_L22N-Pad115)") (class "Default")
      (node (ref "U2") (pin "115") (pinfunction "I/O,_VREF_3,_L22N_115") (pintype "bidirectional"))
    )
    (net (code "224") (name "unconnected-(U2A-I{slash}O,_VREF_3,_L23N_Y-Pad111)") (class "Default")
      (node (ref "U2") (pin "111") (pinfunction "I/O,_VREF_3,_L23N_Y_111") (pintype "bidirectional"))
    )
    (net (code "225") (name "unconnected-(U2A-I{slash}O,_VREF_3-Pad109)") (class "Default")
      (node (ref "U2") (pin "109") (pinfunction "I/O,_VREF_3_109") (pintype "bidirectional"))
    )
    (net (code "226") (name "unconnected-(U2A-I{slash}O,_VREF_4,_L26P_YY-Pad98)") (class "Default")
      (node (ref "U2") (pin "98") (pinfunction "I/O,_VREF_4,_L26P_YY_98") (pintype "bidirectional"))
    )
    (net (code "227") (name "unconnected-(U2A-I{slash}O,_VREF_4,_L27P_Y-Pad94)") (class "Default")
      (node (ref "U2") (pin "94") (pinfunction "I/O,_VREF_4,_L27P_Y_94") (pintype "bidirectional"))
    )
    (net (code "228") (name "unconnected-(U2A-I{slash}O,_VREF_4,_L30P_Y-Pad84)") (class "Default")
      (node (ref "U2") (pin "84") (pinfunction "I/O,_VREF_4,_L30P_Y_84") (pintype "bidirectional"))
    )
    (net (code "229") (name "unconnected-(U2A-I{slash}O,_VREF_4-Pad100)") (class "Default")
      (node (ref "U2") (pin "100") (pinfunction "I/O,_VREF_4_100") (pintype "bidirectional"))
    )
    (net (code "230") (name "unconnected-(U2A-I{slash}O,_VREF_5,_L32P-Pad73)") (class "Default")
      (node (ref "U2") (pin "73") (pinfunction "I/O,_VREF_5,_L32P_73") (pintype "bidirectional"))
    )
    (net (code "231") (name "unconnected-(U2A-I{slash}O,_VREF_5,_L34N_Y-Pad63)") (class "Default")
      (node (ref "U2") (pin "63") (pinfunction "I/O,_VREF_5,_L34N_Y_63") (pintype "bidirectional"))
    )
    (net (code "232") (name "unconnected-(U2A-I{slash}O,_VREF_5,_L36N_YY-Pad59)") (class "Default")
      (node (ref "U2") (pin "59") (pinfunction "I/O,_VREF_5,_L36N_YY_59") (pintype "bidirectional"))
    )
    (net (code "233") (name "unconnected-(U2A-I{slash}O,_VREF_5-Pad57)") (class "Default")
      (node (ref "U2") (pin "57") (pinfunction "I/O,_VREF_5_57") (pintype "bidirectional"))
    )
    (net (code "234") (name "unconnected-(U2A-I{slash}O,_VREF_6,_L43N-Pad31)") (class "Default")
      (node (ref "U2") (pin "31") (pinfunction "I/O,_VREF_6,_L43N_31") (pintype "bidirectional"))
    )
    (net (code "235") (name "unconnected-(U2A-I{slash}O,_VREF_6-Pad47)") (class "Default")
      (node (ref "U2") (pin "47") (pinfunction "I/O,_VREF_6_47") (pintype "bidirectional"))
    )
    (net (code "236") (name "unconnected-(U2A-I{slash}O,_VREF_7,_L45P-Pad20)") (class "Default")
      (node (ref "U2") (pin "20") (pinfunction "I/O,_VREF_7,_L45P_20") (pintype "bidirectional"))
    )
    (net (code "237") (name "unconnected-(U2A-I{slash}O,_VREF_7,_L49P_Y-Pad6)") (class "Default")
      (node (ref "U2") (pin "6") (pinfunction "I/O,_VREF_7,_L49P_Y_6") (pintype "bidirectional"))
    )
    (net (code "238") (name "unconnected-(U2A-I{slash}O,_VREF_7-Pad4)") (class "Default")
      (node (ref "U2") (pin "4") (pinfunction "I/O,_VREF_7_4") (pintype "bidirectional"))
    )
    (net (code "239") (name "unconnected-(U2A-I{slash}O-Pad3)") (class "Default")
      (node (ref "U2") (pin "3") (pinfunction "I/O_3") (pintype "bidirectional"))
    )
    (net (code "240") (name "unconnected-(U2A-I{slash}O-Pad5)") (class "Default")
      (node (ref "U2") (pin "5") (pinfunction "I/O_5") (pintype "bidirectional"))
    )
    (net (code "241") (name "unconnected-(U2A-I{slash}O-Pad8)") (class "Default")
      (node (ref "U2") (pin "8") (pinfunction "I/O_8") (pintype "bidirectional"))
    )
    (net (code "242") (name "unconnected-(U2A-I{slash}O-Pad9)") (class "Default")
      (node (ref "U2") (pin "9") (pinfunction "I/O_9") (pintype "bidirectional"))
    )
    (net (code "243") (name "unconnected-(U2A-I{slash}O-Pad22)") (class "Default")
      (node (ref "U2") (pin "22") (pinfunction "I/O_22") (pintype "bidirectional"))
    )
    (net (code "244") (name "unconnected-(U2A-I{slash}O-Pad29)") (class "Default")
      (node (ref "U2") (pin "29") (pinfunction "I/O_29") (pintype "bidirectional"))
    )
    (net (code "245") (name "unconnected-(U2A-I{slash}O-Pad58)") (class "Default")
      (node (ref "U2") (pin "58") (pinfunction "I/O_58") (pintype "bidirectional"))
    )
    (net (code "246") (name "unconnected-(U2A-I{slash}O-Pad70)") (class "Default")
      (node (ref "U2") (pin "70") (pinfunction "I/O_70") (pintype "bidirectional"))
    )
    (net (code "247") (name "unconnected-(U2A-I{slash}O-Pad74)") (class "Default")
      (node (ref "U2") (pin "74") (pinfunction "I/O_74") (pintype "bidirectional"))
    )
    (net (code "248") (name "unconnected-(U2A-I{slash}O-Pad82)") (class "Default")
      (node (ref "U2") (pin "82") (pinfunction "I/O_82") (pintype "bidirectional"))
    )
    (net (code "249") (name "unconnected-(U2A-I{slash}O-Pad95)") (class "Default")
      (node (ref "U2") (pin "95") (pinfunction "I/O_95") (pintype "bidirectional"))
    )
    (net (code "250") (name "unconnected-(U2A-I{slash}O-Pad96)") (class "Default")
      (node (ref "U2") (pin "96") (pinfunction "I/O_96") (pintype "bidirectional"))
    )
    (net (code "251") (name "unconnected-(U2A-I{slash}O-Pad99)") (class "Default")
      (node (ref "U2") (pin "99") (pinfunction "I/O_99") (pintype "bidirectional"))
    )
    (net (code "252") (name "unconnected-(U2A-I{slash}O-Pad110)") (class "Default")
      (node (ref "U2") (pin "110") (pinfunction "I/O_110") (pintype "bidirectional"))
    )
    (net (code "253") (name "unconnected-(U2A-I{slash}O-Pad113)") (class "Default")
      (node (ref "U2") (pin "113") (pinfunction "I/O_113") (pintype "bidirectional"))
    )
    (net (code "254") (name "unconnected-(U2A-I{slash}O-Pad114)") (class "Default")
      (node (ref "U2") (pin "114") (pinfunction "I/O_114") (pintype "bidirectional"))
    )
    (net (code "255") (name "unconnected-(U2A-I{slash}O-Pad127)") (class "Default")
      (node (ref "U2") (pin "127") (pinfunction "I/O_127") (pintype "bidirectional"))
    )
    (net (code "256") (name "unconnected-(U2A-I{slash}O-Pad134)") (class "Default")
      (node (ref "U2") (pin "134") (pinfunction "I/O_134") (pintype "bidirectional"))
    )
    (net (code "257") (name "unconnected-(U2A-I{slash}O-Pad147)") (class "Default")
      (node (ref "U2") (pin "147") (pinfunction "I/O_147") (pintype "bidirectional"))
    )
    (net (code "258") (name "unconnected-(U2A-I{slash}O-Pad148)") (class "Default")
      (node (ref "U2") (pin "148") (pinfunction "I/O_148") (pintype "bidirectional"))
    )
    (net (code "259") (name "unconnected-(U2A-I{slash}O-Pad149)") (class "Default")
      (node (ref "U2") (pin "149") (pinfunction "I/O_149") (pintype "bidirectional"))
    )
    (net (code "260") (name "unconnected-(U2A-I{slash}O-Pad163)") (class "Default")
      (node (ref "U2") (pin "163") (pinfunction "I/O_163") (pintype "bidirectional"))
    )
    (net (code "261") (name "unconnected-(U2A-I{slash}O-Pad166)") (class "Default")
      (node (ref "U2") (pin "166") (pinfunction "I/O_166") (pintype "bidirectional"))
    )
    (net (code "262") (name "unconnected-(U2A-I{slash}O-Pad167)") (class "Default")
      (node (ref "U2") (pin "167") (pinfunction "I/O_167") (pintype "bidirectional"))
    )
    (net (code "263") (name "unconnected-(U2A-I{slash}O-Pad180)") (class "Default")
      (node (ref "U2") (pin "180") (pinfunction "I/O_180") (pintype "bidirectional"))
    )
    (net (code "264") (name "unconnected-(U2A-I{slash}O-Pad200)") (class "Default")
      (node (ref "U2") (pin "200") (pinfunction "I/O_200") (pintype "bidirectional"))
    )
    (net (code "265") (name "unconnected-(U2A-I{slash}O-Pad201)") (class "Default")
      (node (ref "U2") (pin "201") (pinfunction "I/O_201") (pintype "bidirectional"))
    )
    (net (code "266") (name "unconnected-(U2A-I{slash}O-Pad204)") (class "Default")
      (node (ref "U2") (pin "204") (pinfunction "I/O_204") (pintype "bidirectional"))
    )
    (net (code "267") (name "unconnected-(U2A-I{slash}O-Pad206)") (class "Default")
      (node (ref "U2") (pin "206") (pinfunction "I/O_206") (pintype "bidirectional"))
    )
    (net (code "268") (name "unconnected-(U2A-I{slash}O_(D1),_L14N-Pad145)") (class "Default")
      (node (ref "U2") (pin "145") (pinfunction "I/O_(D1),_L14N_145") (pintype "bidirectional"))
    )
    (net (code "269") (name "unconnected-(U2A-I{slash}O_(D2),_L15P_YY-Pad141)") (class "Default")
      (node (ref "U2") (pin "141") (pinfunction "I/O_(D2),_L15P_YY_141") (pintype "bidirectional"))
    )
    (net (code "270") (name "unconnected-(U2A-I{slash}O_(D3),_L17N-Pad135)") (class "Default")
      (node (ref "U2") (pin "135") (pinfunction "I/O_(D3),_L17N_135") (pintype "bidirectional"))
    )
    (net (code "271") (name "unconnected-(U2A-I{slash}O_(D4),_L19P-Pad126)") (class "Default")
      (node (ref "U2") (pin "126") (pinfunction "I/O_(D4),_L19P_126") (pintype "bidirectional"))
    )
    (net (code "272") (name "unconnected-(U2A-I{slash}O_(D5),_L21N_YY-Pad120)") (class "Default")
      (node (ref "U2") (pin "120") (pinfunction "I/O_(D5),_L21N_YY_120") (pintype "bidirectional"))
    )
    (net (code "273") (name "unconnected-(U2A-I{slash}O_(D6),_L22P-Pad116)") (class "Default")
      (node (ref "U2") (pin "116") (pinfunction "I/O_(D6),_L22P_116") (pintype "bidirectional"))
    )
    (net (code "274") (name "unconnected-(U2A-I{slash}O_(D7),_L24P_YY-Pad108)") (class "Default")
      (node (ref "U2") (pin "108") (pinfunction "I/O_(D7),_L24P_YY_108") (pintype "bidirectional"))
    )
    (net (code "275") (name "unconnected-(U2A-I{slash}O_(DLL),_L5N-Pad187)") (class "Default")
      (node (ref "U2") (pin "187") (pinfunction "I/O_(DLL),_L5N_187") (pintype "bidirectional"))
    )
    (net (code "276") (name "unconnected-(U2A-I{slash}O_(DLL),_L5P-Pad181)") (class "Default")
      (node (ref "U2") (pin "181") (pinfunction "I/O_(DLL),_L5P_181") (pintype "bidirectional"))
    )
    (net (code "277") (name "unconnected-(U2A-I{slash}O_(DLL),_L31N-Pad75)") (class "Default")
      (node (ref "U2") (pin "75") (pinfunction "I/O_(DLL),_L31N_75") (pintype "bidirectional"))
    )
    (net (code "278") (name "unconnected-(U2A-I{slash}O_(DLL),_L31P-Pad81)") (class "Default")
      (node (ref "U2") (pin "81") (pinfunction "I/O_(DLL),_L31P_81") (pintype "bidirectional"))
    )
    (net (code "279") (name "unconnected-(U2A-I{slash}O_(DOUT,_BUSY),_L12P_YY-Pad154)") (class "Default")
      (node (ref "U2") (pin "154") (pinfunction "I/O_(DOUT,_BUSY),_L12P_YY_154") (pintype "bidirectional"))
    )
    (net (code "280") (name "unconnected-(U2A-I{slash}O_(IRDY),_L18N_YY-Pad132)") (class "Default")
      (node (ref "U2") (pin "132") (pinfunction "I/O_(IRDY),_L18N_YY_132") (pintype "bidirectional"))
    )
    (net (code "281") (name "unconnected-(U2A-I{slash}O_(IRDY),_L44N_YY-Pad24)") (class "Default")
      (node (ref "U2") (pin "24") (pinfunction "I/O_(IRDY),_L44N_YY_24") (pintype "bidirectional"))
    )
    (net (code "282") (name "unconnected-(U2A-I{slash}O_(TRDY)-Pad27)") (class "Default")
      (node (ref "U2") (pin "27") (pinfunction "I/O_(TRDY)_27") (pintype "bidirectional"))
    )
    (net (code "283") (name "unconnected-(U2A-I{slash}O_(TRDY)-Pad129)") (class "Default")
      (node (ref "U2") (pin "129") (pinfunction "I/O_(TRDY)_129") (pintype "bidirectional"))
    )
    (net (code "284") (name "unconnected-(U2A-I{slash}O_(~{CS}),_L11P_YY-Pad160)") (class "Default")
      (node (ref "U2") (pin "160") (pinfunction "I/O_(~{CS}),_L11P_YY_160") (pintype "bidirectional"))
    )
    (net (code "285") (name "unconnected-(U2A-I{slash}O_(~{WRITE}),_L11N_YY-Pad161)") (class "Default")
      (node (ref "U2") (pin "161") (pinfunction "I/O_(~{WRITE}),_L11N_YY_161") (pintype "bidirectional"))
    )
  )
)
